# Wiring_Diagram_2020-10-13_10-57-28.net
KiCad netlist of a schematic drawn in EasyEDA
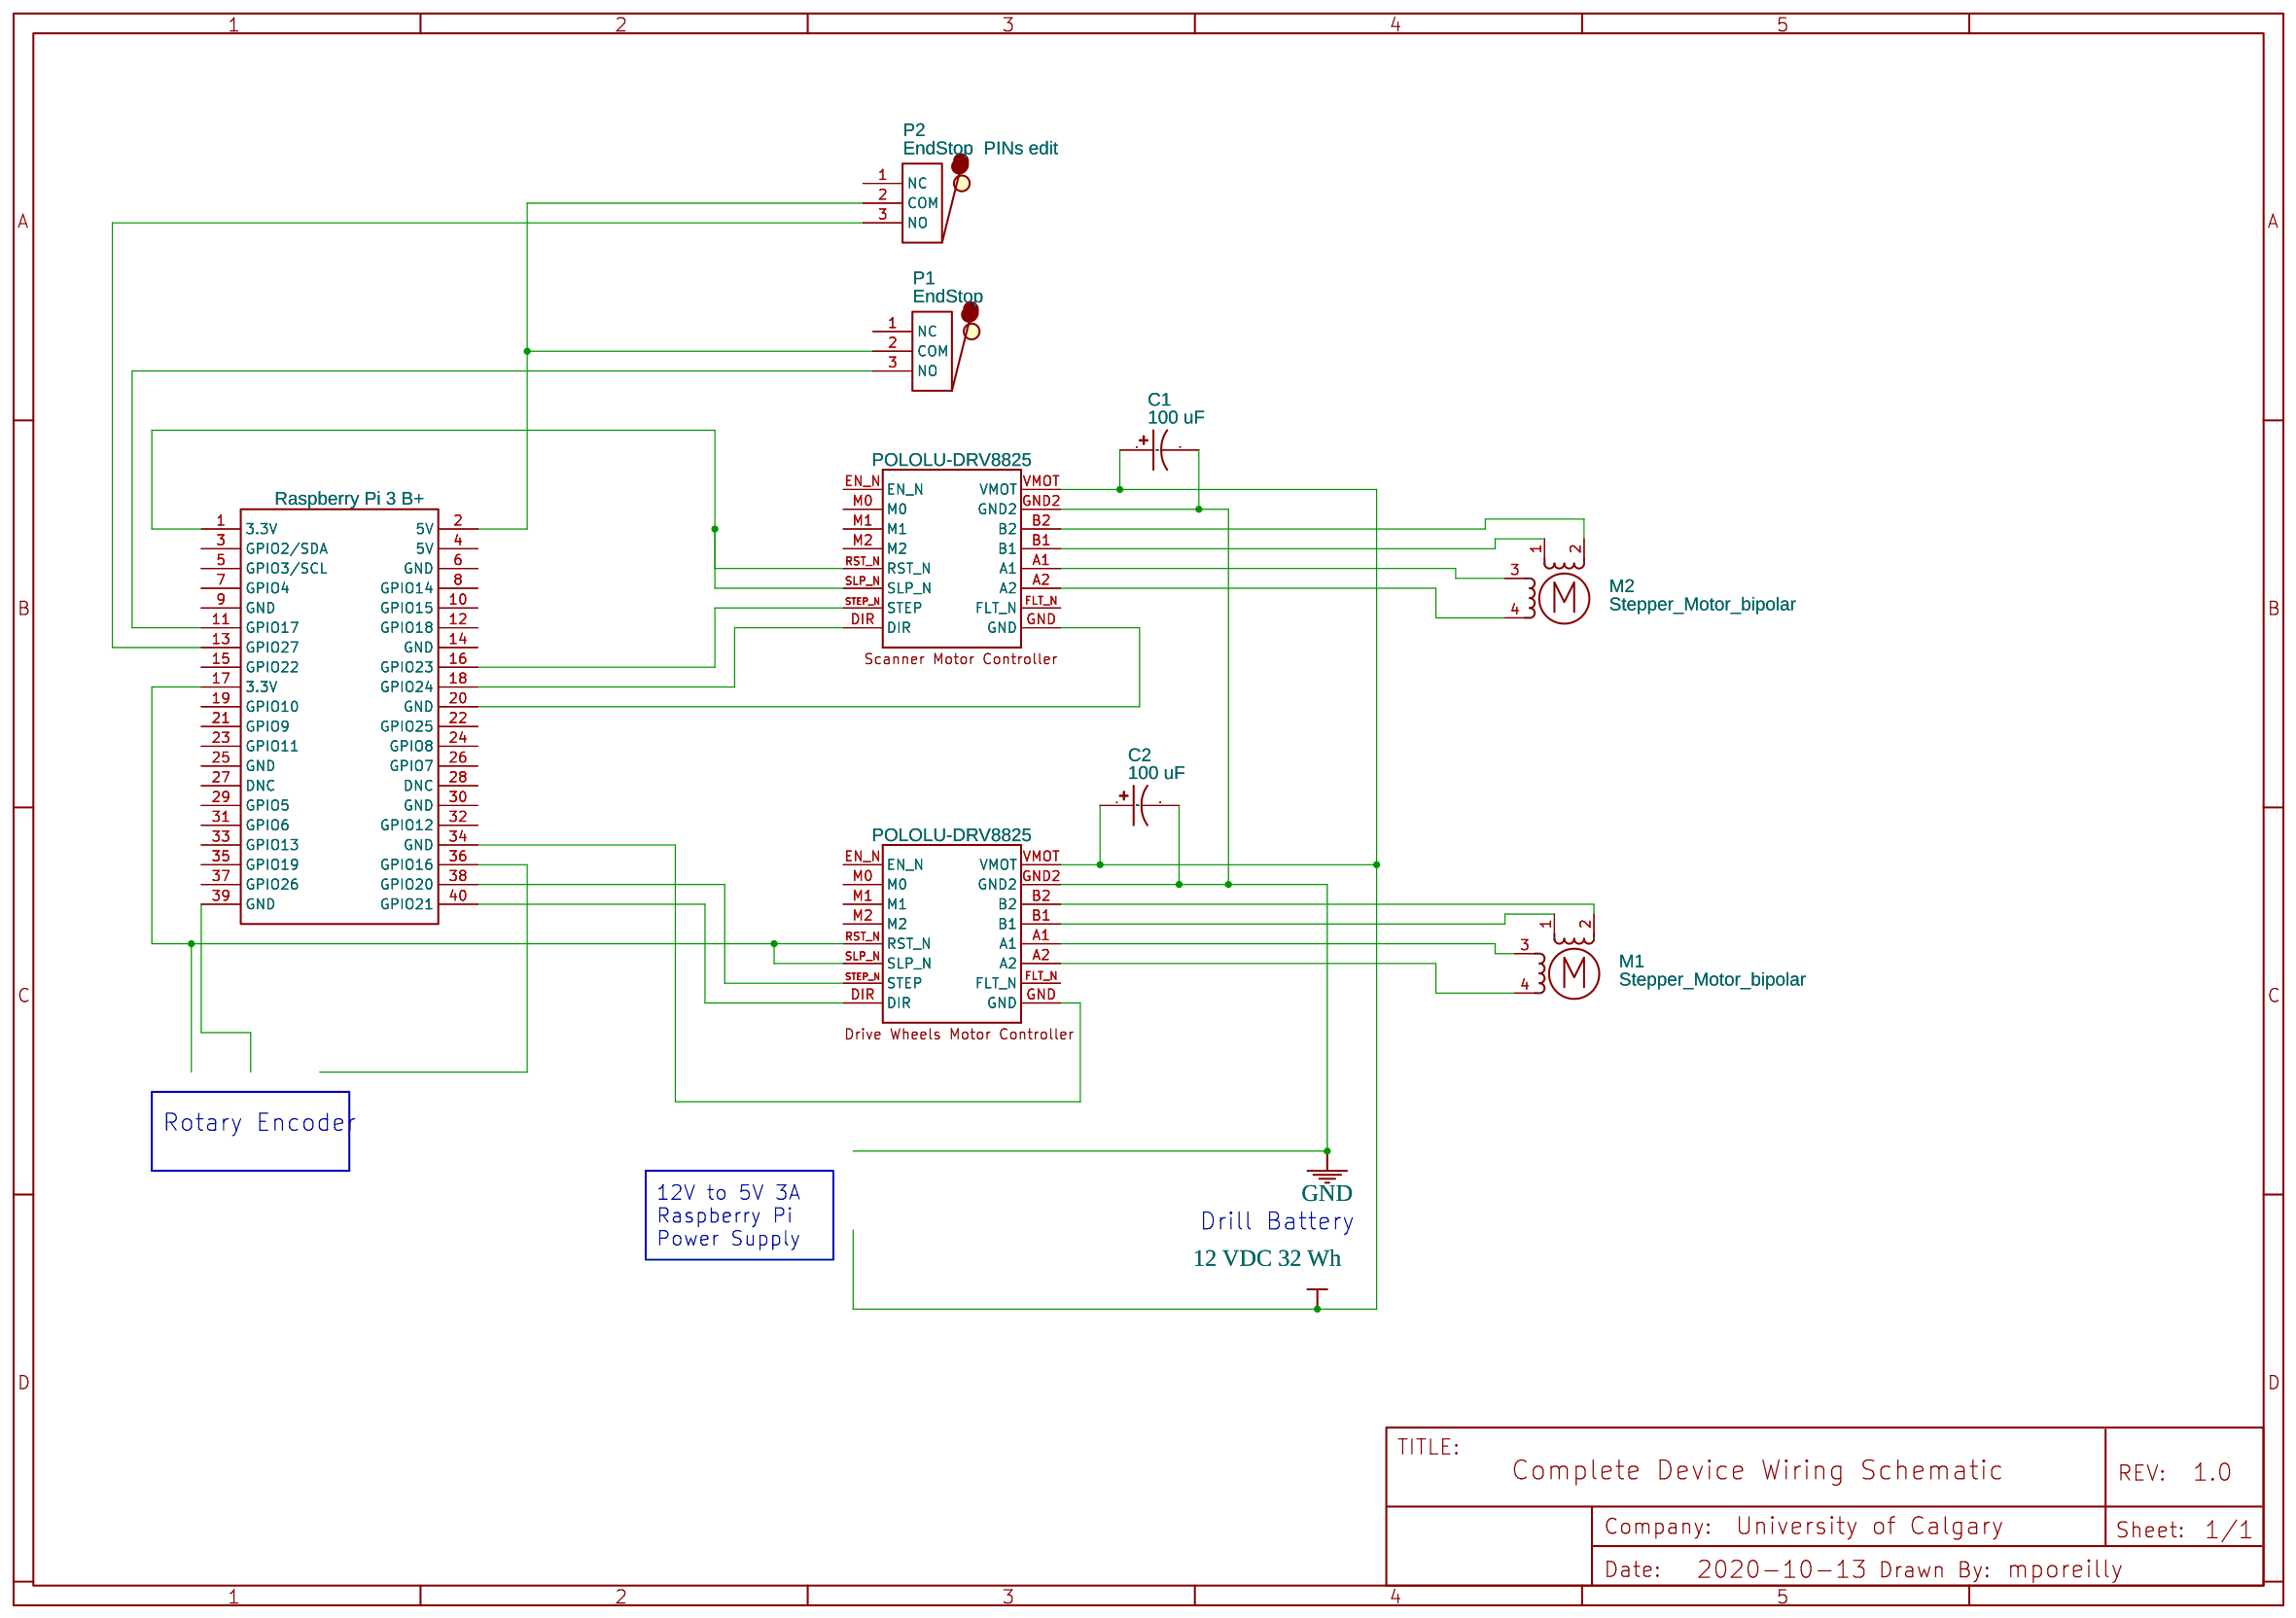
[diagram p0: schematic sheet]

(export (version "E")
  (design (tool "Eeschema 10.0.6"))
  (components
    (comp (ref "C1") (value "100 uF") (libsource (lib "") (part "C_Tan_SMD_A_US")))
    (comp (ref "C2") (value "100 uF") (libsource (lib "") (part "C_Tan_SMD_A_US")))
    (comp (ref "G$1") (value "POLOLU-DRV8825") (libsource (lib "") (part "POLOLU-DRV8825")))
    (comp (ref "G$2") (value "POLOLU-DRV8825") (libsource (lib "") (part "POLOLU-DRV8825_1")))
    (comp (ref "M1") (value "Stepper_Motor_bipolar") (libsource (lib "") (part "Stepper_Motor_bipolar")))
    (comp (ref "M2") (value "Stepper_Motor_bipolar") (libsource (lib "") (part "Stepper_Motor_bipolar")))
    (comp (ref "P1") (value "EndStop") (libsource (lib "") (part "EndStop  PINs edit")))
    (comp (ref "P2")
      (value "EndStop  PINs edit")
      (fields (field (name "BOM_Manufacturer Part") "EndStop"))
      (libsource (lib "") (part "EndStop  PINs edit"))
    )
    (comp (ref "RPI1")
      (value "Raspberry Pi 3 B+")
      (fields
        (field (name "Manufacturer") "Raspberry Pi")
        (field (name "BOM_Manufacturer Part") "Raspberry Pi 3 - Model B+ - 1.4GHz Cortex-A53 with 1GB RAM")
        (field (name "BOM_Supplier Part") "3775")
      )
      (libsource (lib "") (part "Raspberry Pi 3 B+"))
    )
  )
  (nets
    (net (code "1") (name "12 VDC 32 Wh") (class "Default")
      (node (ref "C1") (pin "1") (pinfunction "1_1") (pintype "unspecified"))
      (node (ref "C2") (pin "1") (pinfunction "1_1") (pintype "unspecified"))
      (node (ref "G$1") (pin "VMOT") (pinfunction "VMOT_VMOT") (pintype "bidirectional"))
      (node (ref "G$2") (pin "VMOT") (pinfunction "VMOT_VMOT") (pintype "bidirectional"))
    )
    (net (code "2") (name "GND") (class "Default")
      (node (ref "C1") (pin "2") (pinfunction "2_2") (pintype "unspecified"))
      (node (ref "C2") (pin "2") (pinfunction "2_2") (pintype "unspecified"))
      (node (ref "G$1") (pin "GND2") (pinfunction "GND2_GND2") (pintype "bidirectional"))
      (node (ref "G$2") (pin "GND2") (pinfunction "GND2_GND2") (pintype "bidirectional"))
    )
    (net (code "3") (name "Net-(G$1-PadA1)") (class "Default")
      (node (ref "G$1") (pin "A1") (pinfunction "A1_A1") (pintype "bidirectional"))
      (node (ref "M2") (pin "3") (pinfunction "3_3") (pintype "unspecified"))
    )
    (net (code "4") (name "Net-(G$1-PadA2)") (class "Default")
      (node (ref "G$1") (pin "A2") (pinfunction "A2_A2") (pintype "bidirectional"))
      (node (ref "M2") (pin "4") (pinfunction "4_4") (pintype "unspecified"))
    )
    (net (code "5") (name "Net-(G$1-PadB1)") (class "Default")
      (node (ref "G$1") (pin "B1") (pinfunction "B1_B1") (pintype "bidirectional"))
      (node (ref "M2") (pin "1") (pinfunction "1_1") (pintype "unspecified"))
    )
    (net (code "6") (name "Net-(G$1-PadB2)") (class "Default")
      (node (ref "G$1") (pin "B2") (pinfunction "B2_B2") (pintype "bidirectional"))
      (node (ref "M2") (pin "2") (pinfunction "2_2") (pintype "unspecified"))
    )
    (net (code "7") (name "Net-(G$1-PadGND)") (class "Default")
      (node (ref "G$1") (pin "GND") (pinfunction "GND_GND") (pintype "bidirectional"))
      (node (ref "RPI1") (pin "20") (pinfunction "GND_20") (pintype "unspecified"))
    )
    (net (code "8") (name "Net-(G$1-PadRST_N)") (class "Default")
      (node (ref "G$1") (pin "RST_N") (pinfunction "RST_N_RST_N") (pintype "bidirectional"))
      (node (ref "G$1") (pin "SLP_N") (pinfunction "SLP_N_SLP_N") (pintype "bidirectional"))
      (node (ref "RPI1") (pin "1") (pinfunction "3.3V_1") (pintype "passive"))
    )
    (net (code "9") (name "Net-(G$1-STEP)") (class "Default")
      (node (ref "G$1") (pin "STEP_N") (pinfunction "STEP_STEP_N") (pintype "bidirectional"))
      (node (ref "RPI1") (pin "16") (pinfunction "GPIO23_16") (pintype "bidirectional"))
    )
    (net (code "10") (name "Net-(G$2-PadA1)") (class "Default")
      (node (ref "G$2") (pin "A1") (pinfunction "A1_A1") (pintype "bidirectional"))
      (node (ref "M1") (pin "3") (pinfunction "3_3") (pintype "unspecified"))
    )
    (net (code "11") (name "Net-(G$2-PadA2)") (class "Default")
      (node (ref "G$2") (pin "A2") (pinfunction "A2_A2") (pintype "bidirectional"))
      (node (ref "M1") (pin "4") (pinfunction "4_4") (pintype "unspecified"))
    )
    (net (code "12") (name "Net-(G$2-PadB1)") (class "Default")
      (node (ref "G$2") (pin "B1") (pinfunction "B1_B1") (pintype "bidirectional"))
      (node (ref "M1") (pin "1") (pinfunction "1_1") (pintype "unspecified"))
    )
    (net (code "13") (name "Net-(G$2-PadB2)") (class "Default")
      (node (ref "G$2") (pin "B2") (pinfunction "B2_B2") (pintype "bidirectional"))
      (node (ref "M1") (pin "2") (pinfunction "2_2") (pintype "unspecified"))
    )
    (net (code "14") (name "Net-(G$2-PadGND)") (class "Default")
      (node (ref "G$2") (pin "GND") (pinfunction "GND_GND") (pintype "bidirectional"))
      (node (ref "RPI1") (pin "34") (pinfunction "GND_34") (pintype "unspecified"))
    )
    (net (code "15") (name "Net-(G$2-PadRST_N)") (class "Default")
      (node (ref "G$2") (pin "RST_N") (pinfunction "RST_N_RST_N") (pintype "bidirectional"))
      (node (ref "G$2") (pin "SLP_N") (pinfunction "SLP_N_SLP_N") (pintype "bidirectional"))
      (node (ref "RPI1") (pin "17") (pinfunction "3.3V_17") (pintype "passive"))
    )
    (net (code "16") (name "Net-(G$2-STEP)") (class "Default")
      (node (ref "G$2") (pin "STEP_N") (pinfunction "STEP_STEP_N") (pintype "bidirectional"))
      (node (ref "RPI1") (pin "38") (pinfunction "GPIO20_38") (pintype "bidirectional"))
    )
    (net (code "17") (name "Net-(P1-COM)") (class "Default")
      (node (ref "P1") (pin "2") (pinfunction "COM_2") (pintype "unspecified"))
      (node (ref "P2") (pin "2") (pinfunction "COM_2") (pintype "unspecified"))
      (node (ref "RPI1") (pin "2") (pinfunction "5V_2") (pintype "passive"))
    )
    (net (code "18") (name "Net-(P1-NO)") (class "Default")
      (node (ref "P1") (pin "3") (pinfunction "NO_3") (pintype "unspecified"))
      (node (ref "RPI1") (pin "11") (pinfunction "GPIO17_11") (pintype "bidirectional"))
    )
    (net (code "19") (name "Net-(P2-NO)") (class "Default")
      (node (ref "P2") (pin "3") (pinfunction "NO_3") (pintype "unspecified"))
      (node (ref "RPI1") (pin "13") (pinfunction "GPIO27_13") (pintype "bidirectional"))
    )
    (net (code "20") (name "Net-(RPI1-GPIO21)") (class "Default")
      (node (ref "G$2") (pin "DIR") (pinfunction "DIR_DIR") (pintype "bidirectional"))
      (node (ref "RPI1") (pin "40") (pinfunction "GPIO21_40") (pintype "bidirectional"))
    )
    (net (code "21") (name "Net-(RPI1-GPIO24)") (class "Default")
      (node (ref "G$1") (pin "DIR") (pinfunction "DIR_DIR") (pintype "bidirectional"))
      (node (ref "RPI1") (pin "18") (pinfunction "GPIO24_18") (pintype "bidirectional"))
    )
    (net (code "22") (name "unconnected-(G$1-PadEN_N)") (class "Default")
      (node (ref "G$1") (pin "EN_N") (pinfunction "EN_N_EN_N") (pintype "bidirectional"))
    )
    (net (code "23") (name "unconnected-(G$1-PadFLT_N)") (class "Default")
      (node (ref "G$1") (pin "FLT_N") (pinfunction "FLT_N_FLT_N") (pintype "bidirectional"))
    )
    (net (code "24") (name "unconnected-(G$1-PadM0)") (class "Default")
      (node (ref "G$1") (pin "M0") (pinfunction "M0_M0") (pintype "bidirectional"))
    )
    (net (code "25") (name "unconnected-(G$1-PadM1)") (class "Default")
      (node (ref "G$1") (pin "M1") (pinfunction "M1_M1") (pintype "bidirectional"))
    )
    (net (code "26") (name "unconnected-(G$1-PadM2)") (class "Default")
      (node (ref "G$1") (pin "M2") (pinfunction "M2_M2") (pintype "bidirectional"))
    )
    (net (code "27") (name "unconnected-(G$2-PadEN_N)") (class "Default")
      (node (ref "G$2") (pin "EN_N") (pinfunction "EN_N_EN_N") (pintype "bidirectional"))
    )
    (net (code "28") (name "unconnected-(G$2-PadFLT_N)") (class "Default")
      (node (ref "G$2") (pin "FLT_N") (pinfunction "FLT_N_FLT_N") (pintype "bidirectional"))
    )
    (net (code "29") (name "unconnected-(G$2-PadM0)") (class "Default")
      (node (ref "G$2") (pin "M0") (pinfunction "M0_M0") (pintype "bidirectional"))
    )
    (net (code "30") (name "unconnected-(G$2-PadM1)") (class "Default")
      (node (ref "G$2") (pin "M1") (pinfunction "M1_M1") (pintype "bidirectional"))
    )
    (net (code "31") (name "unconnected-(G$2-PadM2)") (class "Default")
      (node (ref "G$2") (pin "M2") (pinfunction "M2_M2") (pintype "bidirectional"))
    )
    (net (code "32") (name "unconnected-(P1-NC-Pad1)") (class "Default")
      (node (ref "P1") (pin "1") (pinfunction "NC_1") (pintype "unspecified"))
    )
    (net (code "33") (name "unconnected-(P2-NC-Pad1)") (class "Default")
      (node (ref "P2") (pin "1") (pinfunction "NC_1") (pintype "unspecified"))
    )
    (net (code "34") (name "unconnected-(RPI1-5V-Pad4)") (class "Default")
      (node (ref "RPI1") (pin "4") (pinfunction "5V_4") (pintype "passive"))
    )
    (net (code "35") (name "unconnected-(RPI1-DNC-Pad27)") (class "Default")
      (node (ref "RPI1") (pin "27") (pinfunction "DNC_27") (pintype "unspecified"))
    )
    (net (code "36") (name "unconnected-(RPI1-DNC-Pad28)") (class "Default")
      (node (ref "RPI1") (pin "28") (pinfunction "DNC_28") (pintype "unspecified"))
    )
    (net (code "37") (name "unconnected-(RPI1-GND-Pad6)") (class "Default")
      (node (ref "RPI1") (pin "6") (pinfunction "GND_6") (pintype "unspecified"))
    )
    (net (code "38") (name "unconnected-(RPI1-GND-Pad9)") (class "Default")
      (node (ref "RPI1") (pin "9") (pinfunction "GND_9") (pintype "unspecified"))
    )
    (net (code "39") (name "unconnected-(RPI1-GND-Pad14)") (class "Default")
      (node (ref "RPI1") (pin "14") (pinfunction "GND_14") (pintype "unspecified"))
    )
    (net (code "40") (name "unconnected-(RPI1-GND-Pad25)") (class "Default")
      (node (ref "RPI1") (pin "25") (pinfunction "GND_25") (pintype "unspecified"))
    )
    (net (code "41") (name "unconnected-(RPI1-GND-Pad30)") (class "Default")
      (node (ref "RPI1") (pin "30") (pinfunction "GND_30") (pintype "unspecified"))
    )
    (net (code "42") (name "unconnected-(RPI1-GND-Pad39)") (class "Default")
      (node (ref "RPI1") (pin "39") (pinfunction "GND_39") (pintype "unspecified"))
    )
    (net (code "43") (name "unconnected-(RPI1-GPIO2{slash}SDA-Pad3)") (class "Default")
      (node (ref "RPI1") (pin "3") (pinfunction "GPIO2/SDA_3") (pintype "bidirectional"))
    )
    (net (code "44") (name "unconnected-(RPI1-GPIO3{slash}SCL-Pad5)") (class "Default")
      (node (ref "RPI1") (pin "5") (pinfunction "GPIO3/SCL_5") (pintype "bidirectional"))
    )
    (net (code "45") (name "unconnected-(RPI1-GPIO4-Pad7)") (class "Default")
      (node (ref "RPI1") (pin "7") (pinfunction "GPIO4_7") (pintype "bidirectional"))
    )
    (net (code "46") (name "unconnected-(RPI1-GPIO5-Pad29)") (class "Default")
      (node (ref "RPI1") (pin "29") (pinfunction "GPIO5_29") (pintype "bidirectional"))
    )
    (net (code "47") (name "unconnected-(RPI1-GPIO6-Pad31)") (class "Default")
      (node (ref "RPI1") (pin "31") (pinfunction "GPIO6_31") (pintype "bidirectional"))
    )
    (net (code "48") (name "unconnected-(RPI1-GPIO7-Pad26)") (class "Default")
      (node (ref "RPI1") (pin "26") (pinfunction "GPIO7_26") (pintype "bidirectional"))
    )
    (net (code "49") (name "unconnected-(RPI1-GPIO8-Pad24)") (class "Default")
      (node (ref "RPI1") (pin "24") (pinfunction "GPIO8_24") (pintype "bidirectional"))
    )
    (net (code "50") (name "unconnected-(RPI1-GPIO9-Pad21)") (class "Default")
      (node (ref "RPI1") (pin "21") (pinfunction "GPIO9_21") (pintype "bidirectional"))
    )
    (net (code "51") (name "unconnected-(RPI1-GPIO10-Pad19)") (class "Default")
      (node (ref "RPI1") (pin "19") (pinfunction "GPIO10_19") (pintype "bidirectional"))
    )
    (net (code "52") (name "unconnected-(RPI1-GPIO11-Pad23)") (class "Default")
      (node (ref "RPI1") (pin "23") (pinfunction "GPIO11_23") (pintype "bidirectional"))
    )
    (net (code "53") (name "unconnected-(RPI1-GPIO12-Pad32)") (class "Default")
      (node (ref "RPI1") (pin "32") (pinfunction "GPIO12_32") (pintype "bidirectional"))
    )
    (net (code "54") (name "unconnected-(RPI1-GPIO13-Pad33)") (class "Default")
      (node (ref "RPI1") (pin "33") (pinfunction "GPIO13_33") (pintype "bidirectional"))
    )
    (net (code "55") (name "unconnected-(RPI1-GPIO14-Pad8)") (class "Default")
      (node (ref "RPI1") (pin "8") (pinfunction "GPIO14_8") (pintype "bidirectional"))
    )
    (net (code "56") (name "unconnected-(RPI1-GPIO15-Pad10)") (class "Default")
      (node (ref "RPI1") (pin "10") (pinfunction "GPIO15_10") (pintype "bidirectional"))
    )
    (net (code "57") (name "unconnected-(RPI1-GPIO16-Pad36)") (class "Default")
      (node (ref "RPI1") (pin "36") (pinfunction "GPIO16_36") (pintype "bidirectional"))
    )
    (net (code "58") (name "unconnected-(RPI1-GPIO18-Pad12)") (class "Default")
      (node (ref "RPI1") (pin "12") (pinfunction "GPIO18_12") (pintype "bidirectional"))
    )
    (net (code "59") (name "unconnected-(RPI1-GPIO19-Pad35)") (class "Default")
      (node (ref "RPI1") (pin "35") (pinfunction "GPIO19_35") (pintype "bidirectional"))
    )
    (net (code "60") (name "unconnected-(RPI1-GPIO22-Pad15)") (class "Default")
      (node (ref "RPI1") (pin "15") (pinfunction "GPIO22_15") (pintype "bidirectional"))
    )
    (net (code "61") (name "unconnected-(RPI1-GPIO25-Pad22)") (class "Default")
      (node (ref "RPI1") (pin "22") (pinfunction "GPIO25_22") (pintype "bidirectional"))
    )
    (net (code "62") (name "unconnected-(RPI1-GPIO26-Pad37)") (class "Default")
      (node (ref "RPI1") (pin "37") (pinfunction "GPIO26_37") (pintype "bidirectional"))
    )
  )
)
